# C51_led.net
KiCad netlist of a schematic drawn in Altium Designer
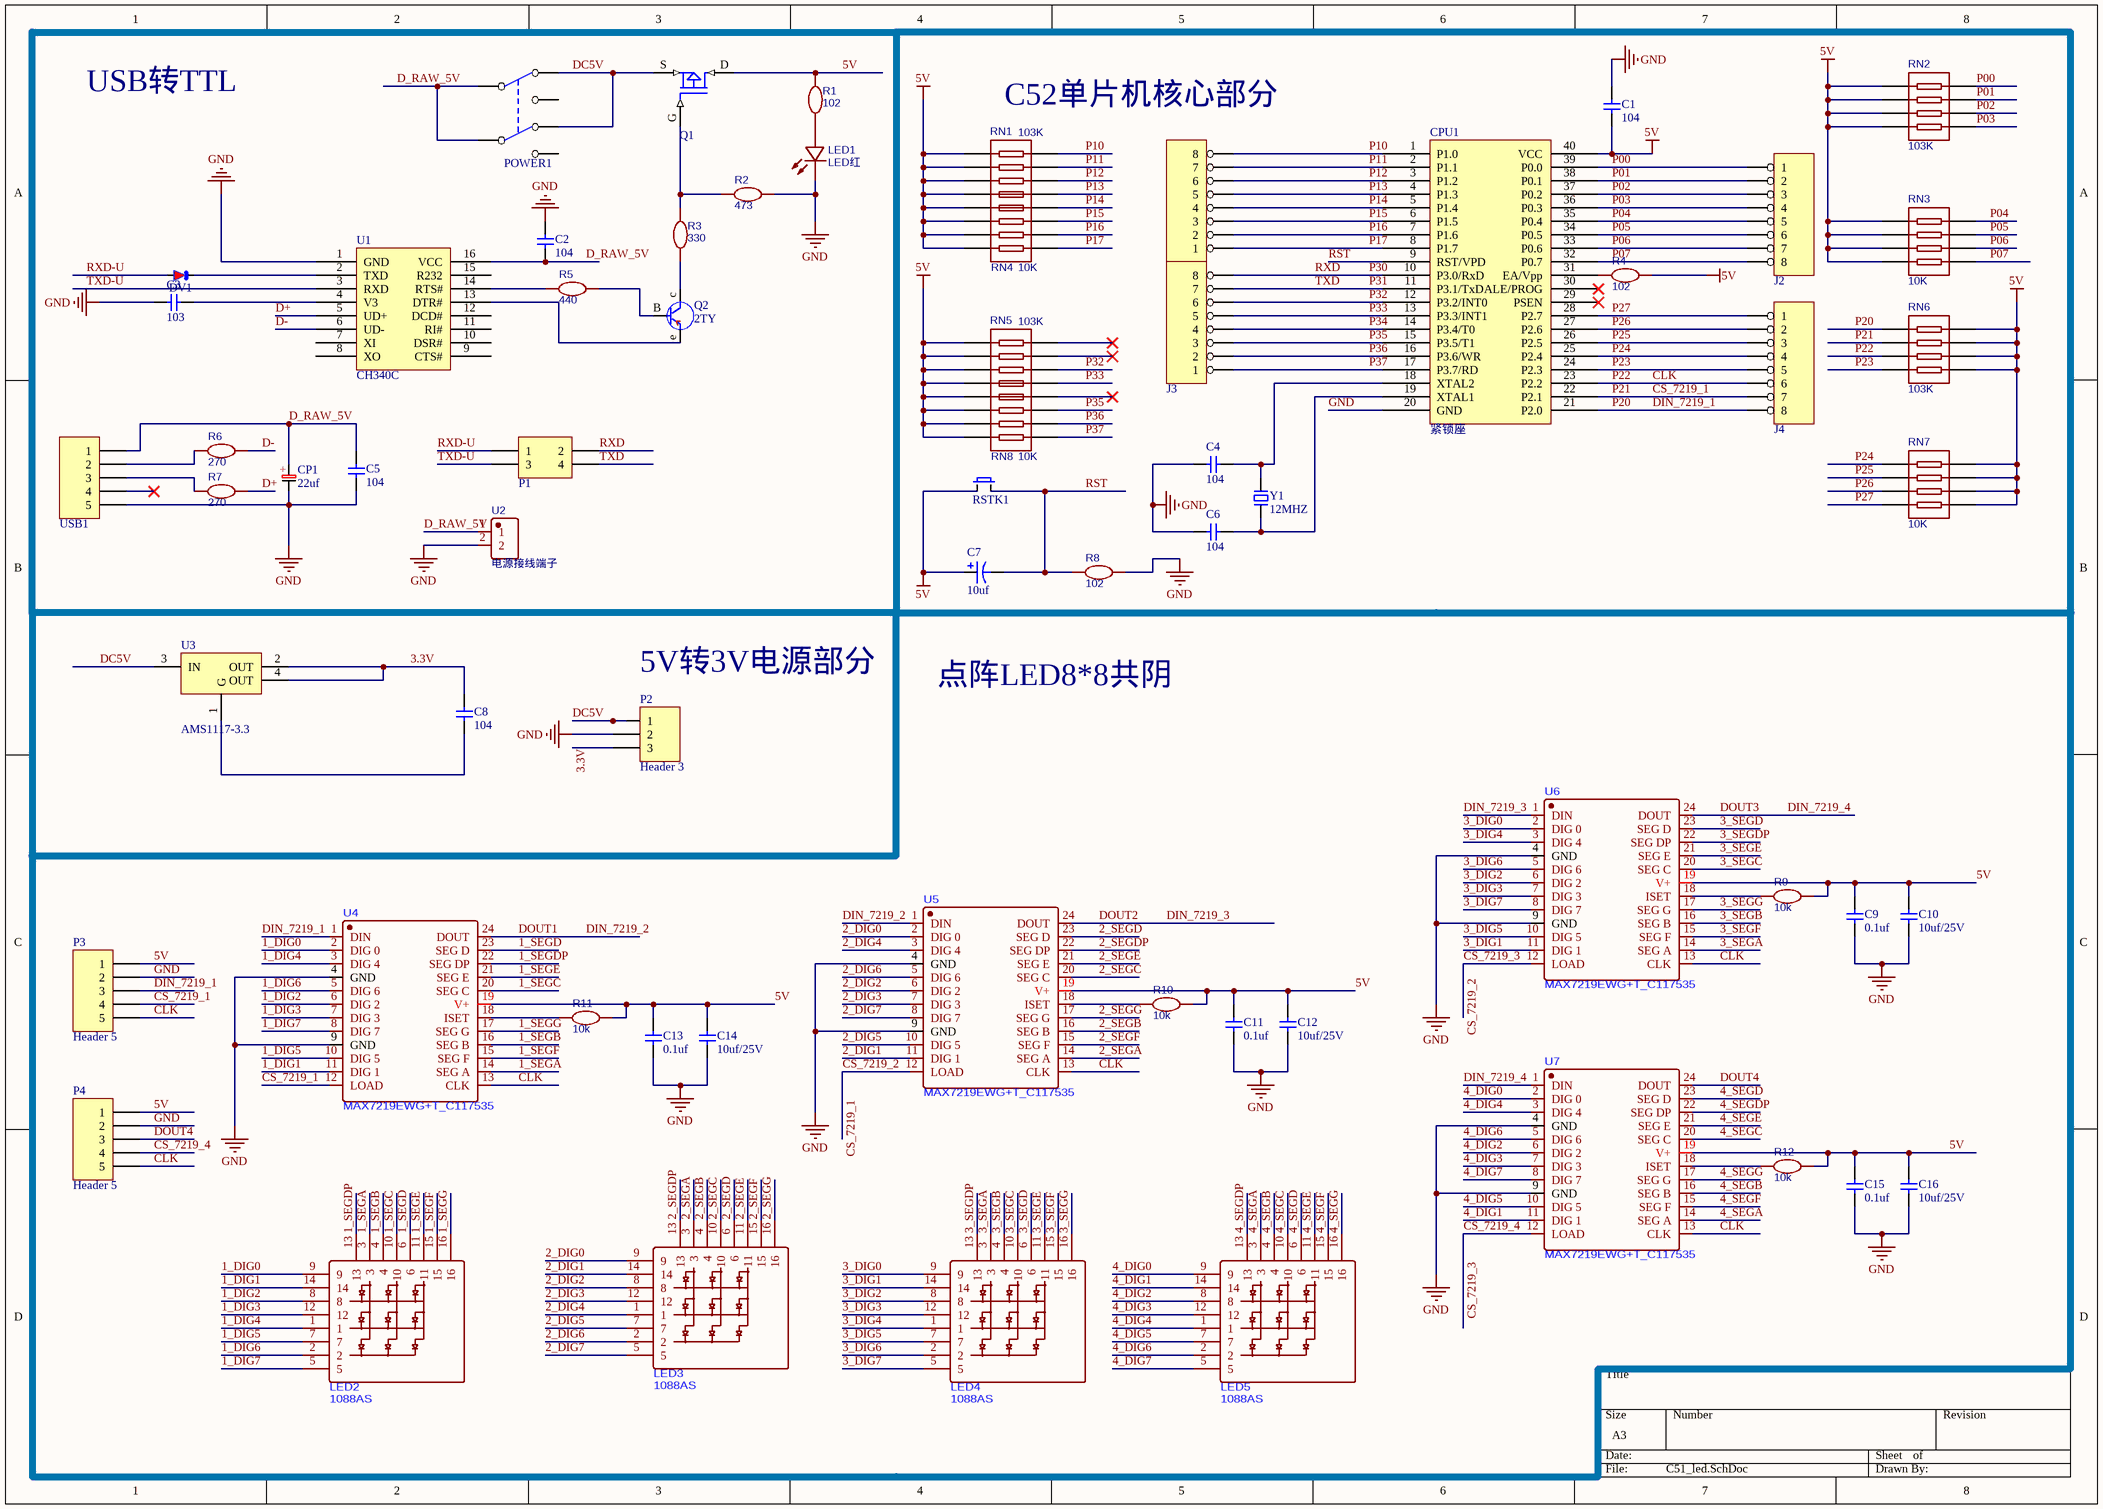
[diagram p0: C51_led.SchDoc]

(export (version "E")
  (design (tool "Eeschema 10.0.6"))
  (components
    (comp (ref "C1") (value "104") (footprint "C1206") (libsource (lib "童有为sch") (part "CAP")))
    (comp (ref "C2") (value "104") (footprint "C1206") (libsource (lib "童有为sch") (part "CAP")))
    (comp (ref "C3") (value "103") (footprint "C1206") (libsource (lib "童有为sch") (part "CAP")))
    (comp (ref "C4") (value "104") (footprint "C1206") (libsource (lib "童有为sch") (part "CAP")))
    (comp (ref "C5") (value "104") (footprint "C1206") (libsource (lib "童有为sch") (part "CAP")))
    (comp (ref "C6") (value "104") (footprint "C1206") (libsource (lib "童有为sch") (part "CAP")))
    (comp (ref "C7")
      (value "10uf")
      (footprint "CD4")
      (description "Polarized Capacitor (Radial)")
      (fields (field (name "PUBLISHER") "*"))
      (libsource (lib "普中-2&普中-3&普中-4封装库") (part "Cap Pol1"))
    )
    (comp (ref "C8") (value "104") (footprint "C1206") (libsource (lib "童有为sch") (part "CAP")))
    (comp (ref "C9") (value "0.1uf") (footprint "C1206") (libsource (lib "童有为sch") (part "CAP")))
    (comp (ref "C10") (value "10uf/25V") (footprint "C1206") (libsource (lib "童有为sch") (part "CAP")))
    (comp (ref "C11") (value "0.1uf") (footprint "C1206") (libsource (lib "童有为sch") (part "CAP")))
    (comp (ref "C12") (value "10uf/25V") (footprint "C1206") (libsource (lib "童有为sch") (part "CAP")))
    (comp (ref "C13") (value "0.1uf") (footprint "C1206") (libsource (lib "童有为sch") (part "CAP")))
    (comp (ref "C14") (value "10uf/25V") (footprint "C1206") (libsource (lib "童有为sch") (part "CAP")))
    (comp (ref "C15") (value "0.1uf") (footprint "C1206") (libsource (lib "童有为sch") (part "CAP")))
    (comp (ref "C16") (value "10uf/25V") (footprint "C1206") (libsource (lib "童有为sch") (part "CAP")))
    (comp (ref "CP1") (value "22uf") (footprint "CD4") (libsource (lib "普中-2&普中-3&普中-4封装库") (part "CD")))
    (comp (ref "CPU1")
      (value "紧锁座")
      (footprint "ZIF40 - D")
      (description "U")
      (libsource (lib "普中-2&普中-3&普中-4封装库") (part "89C51"))
    )
    (comp (ref "DV1") (value "IN4148") (footprint "D1808A") (libsource (lib "普中-2&普中-3&普中-4封装库") (part "D")))
    (comp (ref "J1")
      (value "SIP8")
      (footprint "SIP8")
      (description "8 Pin Header")
      (libsource (lib "普中-2&普中-3&普中-4封装库") (part "8 HEADER"))
    )
    (comp (ref "J2")
      (value "SIP8")
      (footprint "SIP8")
      (description "8 Pin Header")
      (libsource (lib "") (part "8 HEADER_1"))
    )
    (comp (ref "J3")
      (value "SIP8")
      (footprint "SIP8")
      (description "8 Pin Header")
      (libsource (lib "普中-2&普中-3&普中-4封装库") (part "8 HEADER"))
    )
    (comp (ref "J4")
      (value "SIP8")
      (footprint "SIP8")
      (description "8 Pin Header")
      (libsource (lib "") (part "8 HEADER_1"))
    )
    (comp (ref "LED1")
      (value "LED红")
      (footprint "LED1206-R-RD")
      (fields
        (field (name "BOM_SUPPLIER PART") "C268276")
        (field (name "BOM_MANUFACTURER PART") "OSR51206C1E")
        (field (name "CONTRIBUTOR") "LCSC")
      )
      (libsource (lib "LED_1206") (part "OSR51206C1E"))
    )
    (comp (ref "LED2") (value "1088AS") (footprint "1088AS") (libsource (lib "1088AS") (part "1088AS")))
    (comp (ref "LED3") (value "1088AS") (footprint "1088AS") (libsource (lib "1088AS") (part "1088AS")))
    (comp (ref "LED4") (value "1088AS") (footprint "1088AS") (libsource (lib "1088AS") (part "1088AS")))
    (comp (ref "LED5") (value "1088AS") (footprint "1088AS") (libsource (lib "1088AS") (part "1088AS")))
    (comp (ref "P1")
      (value "Header 2X2")
      (footprint "HDR2X2")
      (description "Header, 2-Pin, Dual row")
      (fields (field (name "PUBLISHER") "Altium Limited"))
      (libsource (lib "普中-2&普中-3&普中-4封装库") (part "Header 2X2"))
    )
    (comp (ref "P2")
      (value "Header 3")
      (footprint "HDR1X3")
      (description "Header, 3-Pin")
      (fields (field (name "PUBLISHER") "Altium Limited"))
      (libsource (lib "常用元件2") (part "Header 3"))
    )
    (comp (ref "P3")
      (value "Header 5")
      (footprint "HDR1X5")
      (description "Header, 5-Pin")
      (fields (field (name "PUBLISHER") "Altium Limited"))
      (libsource (lib "常用元件2") (part "Header 5"))
    )
    (comp (ref "P4")
      (value "Header 5")
      (footprint "HDR1X5")
      (description "Header, 5-Pin")
      (fields (field (name "PUBLISHER") "Altium Limited"))
      (libsource (lib "常用元件2") (part "Header 5"))
    )
    (comp (ref "POWER1")
      (value "自锁开关")
      (footprint "SW6")
      (libsource (lib "普中-2&普中-3&普中-4封装库") (part "SW3-DP"))
    )
    (comp (ref "Q1") (value "MOS-P") (footprint "MOS-P") (libsource (lib "普中-2&普中-3&普中-4封装库") (part "MOS-P")))
    (comp (ref "Q2") (value "2TY") (footprint "NPN-2TY") (libsource (lib "普中-2&普中-3&普中-4封装库") (part "8550")))
    (comp (ref "R1")
      (value "102")
      (footprint "R1206")
      (fields
        (field (name "BOM_SUPPLIER PART") "C125917")
        (field (name "BOM_MANUFACTURER PART") "AC1206FR-072ML")
        (field (name "CONTRIBUTOR") "LCSC")
      )
      (libsource (lib "res_1206") (part "AC1206FR-072ML"))
    )
    (comp (ref "R2")
      (value "473")
      (footprint "R1206")
      (fields
        (field (name "BOM_SUPPLIER PART") "C125917")
        (field (name "BOM_MANUFACTURER PART") "AC1206FR-072ML")
        (field (name "CONTRIBUTOR") "LCSC")
      )
      (libsource (lib "res_1206") (part "AC1206FR-072ML"))
    )
    (comp (ref "R3")
      (value "330")
      (footprint "R1206")
      (fields
        (field (name "BOM_SUPPLIER PART") "C125917")
        (field (name "BOM_MANUFACTURER PART") "AC1206FR-072ML")
        (field (name "CONTRIBUTOR") "LCSC")
      )
      (libsource (lib "res_1206") (part "AC1206FR-072ML"))
    )
    (comp (ref "R4")
      (value "102")
      (footprint "R1206")
      (fields
        (field (name "BOM_SUPPLIER PART") "C125917")
        (field (name "BOM_MANUFACTURER PART") "AC1206FR-072ML")
        (field (name "CONTRIBUTOR") "LCSC")
      )
      (libsource (lib "res_1206") (part "AC1206FR-072ML"))
    )
    (comp (ref "R5")
      (value "440")
      (footprint "R1206")
      (fields
        (field (name "BOM_SUPPLIER PART") "C125917")
        (field (name "BOM_MANUFACTURER PART") "AC1206FR-072ML")
        (field (name "CONTRIBUTOR") "LCSC")
      )
      (libsource (lib "res_1206") (part "AC1206FR-072ML"))
    )
    (comp (ref "R6")
      (value "270")
      (footprint "R1206")
      (fields
        (field (name "BOM_SUPPLIER PART") "C125917")
        (field (name "BOM_MANUFACTURER PART") "AC1206FR-072ML")
        (field (name "CONTRIBUTOR") "LCSC")
      )
      (libsource (lib "res_1206") (part "AC1206FR-072ML"))
    )
    (comp (ref "R7")
      (value "270")
      (footprint "R1206")
      (fields
        (field (name "BOM_SUPPLIER PART") "C125917")
        (field (name "BOM_MANUFACTURER PART") "AC1206FR-072ML")
        (field (name "CONTRIBUTOR") "LCSC")
      )
      (libsource (lib "res_1206") (part "AC1206FR-072ML"))
    )
    (comp (ref "R8")
      (value "102")
      (footprint "R1206")
      (fields
        (field (name "BOM_SUPPLIER PART") "C125917")
        (field (name "BOM_MANUFACTURER PART") "AC1206FR-072ML")
        (field (name "CONTRIBUTOR") "LCSC")
      )
      (libsource (lib "res_1206") (part "AC1206FR-072ML"))
    )
    (comp (ref "R9")
      (value "10k")
      (footprint "R1206")
      (fields
        (field (name "BOM_SUPPLIER PART") "C125917")
        (field (name "BOM_MANUFACTURER PART") "AC1206FR-072ML")
        (field (name "CONTRIBUTOR") "LCSC")
      )
      (libsource (lib "res_1206") (part "AC1206FR-072ML"))
    )
    (comp (ref "R10")
      (value "10k")
      (footprint "R1206")
      (fields
        (field (name "BOM_SUPPLIER PART") "C125917")
        (field (name "BOM_MANUFACTURER PART") "AC1206FR-072ML")
        (field (name "CONTRIBUTOR") "LCSC")
      )
      (libsource (lib "res_1206") (part "AC1206FR-072ML"))
    )
    (comp (ref "R11")
      (value "10k")
      (footprint "R1206")
      (fields
        (field (name "BOM_SUPPLIER PART") "C125917")
        (field (name "BOM_MANUFACTURER PART") "AC1206FR-072ML")
        (field (name "CONTRIBUTOR") "LCSC")
      )
      (libsource (lib "res_1206") (part "AC1206FR-072ML"))
    )
    (comp (ref "R12")
      (value "10k")
      (footprint "R1206")
      (fields
        (field (name "BOM_SUPPLIER PART") "C125917")
        (field (name "BOM_MANUFACTURER PART") "AC1206FR-072ML")
        (field (name "CONTRIBUTOR") "LCSC")
      )
      (libsource (lib "res_1206") (part "AC1206FR-072ML"))
    )
    (comp (ref "RN1")
      (value "103K")
      (footprint "RES-ARRAY-SMD_0603-8P-L3.2-W1.6-BL")
      (fields
        (field (name "BOM_MANUFACTURER PART") "4D03WGJ0302T5E")
        (field (name "BOM_SUPPLIER PART") "C25733")
      )
      (libsource (lib "排阻res") (part "3K"))
    )
    (comp (ref "RN2")
      (value "103K")
      (footprint "RES-ARRAY-SMD_0603-8P-L3.2-W1.6-BL")
      (fields
        (field (name "BOM_MANUFACTURER PART") "4D03WGJ0302T5E")
        (field (name "BOM_SUPPLIER PART") "C25733")
      )
      (libsource (lib "排阻res") (part "3K"))
    )
    (comp (ref "RN3")
      (value "10K")
      (footprint "RES-ARRAY-SMD_0603-8P-L3.2-W1.6-BL")
      (fields
        (field (name "BOM_MANUFACTURER PART") "4D03WGJ0302T5E")
        (field (name "BOM_SUPPLIER PART") "C25733")
      )
      (libsource (lib "排阻res") (part "3K"))
    )
    (comp (ref "RN4")
      (value "10K")
      (footprint "RES-ARRAY-SMD_0603-8P-L3.2-W1.6-BL")
      (fields
        (field (name "BOM_MANUFACTURER PART") "4D03WGJ0302T5E")
        (field (name "BOM_SUPPLIER PART") "C25733")
      )
      (libsource (lib "排阻res") (part "3K"))
    )
    (comp (ref "RN5")
      (value "103K")
      (footprint "RES-ARRAY-SMD_0603-8P-L3.2-W1.6-BL")
      (fields
        (field (name "BOM_MANUFACTURER PART") "4D03WGJ0302T5E")
        (field (name "BOM_SUPPLIER PART") "C25733")
      )
      (libsource (lib "排阻res") (part "3K"))
    )
    (comp (ref "RN6")
      (value "103K")
      (footprint "RES-ARRAY-SMD_0603-8P-L3.2-W1.6-BL")
      (fields
        (field (name "BOM_MANUFACTURER PART") "4D03WGJ0302T5E")
        (field (name "BOM_SUPPLIER PART") "C25733")
      )
      (libsource (lib "排阻res") (part "3K"))
    )
    (comp (ref "RN7")
      (value "10K")
      (footprint "RES-ARRAY-SMD_0603-8P-L3.2-W1.6-BL")
      (fields
        (field (name "BOM_MANUFACTURER PART") "4D03WGJ0302T5E")
        (field (name "BOM_SUPPLIER PART") "C25733")
      )
      (libsource (lib "排阻res") (part "3K"))
    )
    (comp (ref "RN8")
      (value "10K")
      (footprint "RES-ARRAY-SMD_0603-8P-L3.2-W1.6-BL")
      (fields
        (field (name "BOM_MANUFACTURER PART") "4D03WGJ0302T5E")
        (field (name "BOM_SUPPLIER PART") "C25733")
      )
      (libsource (lib "排阻res") (part "3K"))
    )
    (comp (ref "RSTK1")
      (value "按键")
      (footprint "JZ-SW2")
      (libsource (lib "普中-2&普中-3&普中-4封装库") (part "JZ-SW2"))
    )
    (comp (ref "U1")
      (value "CH340C")
      (footprint "SOP-16")
      (libsource (lib "普中-2&普中-3&普中-4封装库") (part "CH340G"))
    )
    (comp (ref "U2")
      (value "电源接线端子")
      (footprint "2p_power")
      (fields
        (field (name "BOM_SUPPLIER PART") "C581335")
        (field (name "BOM_MANUFACTURER PART") "DG127R-5.0-02P-14-00A(H)")
        (field (name "CONTRIBUTOR") "LCSC")
      )
      (libsource (lib "接线端子p=5") (part "DG127R-5.0-02P-14-00A(H)"))
    )
    (comp (ref "U3")
      (value "AMS1117-3.3")
      (footprint "SOT261")
      (description "LINER REG")
      (libsource (lib "普中-2&普中-3&普中-4封装库") (part "LM1117"))
    )
    (comp (ref "U4")
      (value "MAX7219EWG+T_C117535")
      (footprint "sop-24")
      (libsource (lib "max7219") (part "MAX7219EWG+T_C117535"))
    )
    (comp (ref "U5")
      (value "MAX7219EWG+T_C117535")
      (footprint "sop-24")
      (libsource (lib "max7219") (part "MAX7219EWG+T_C117535"))
    )
    (comp (ref "U6")
      (value "MAX7219EWG+T_C117535")
      (footprint "sop-24")
      (libsource (lib "max7219") (part "MAX7219EWG+T_C117535"))
    )
    (comp (ref "U7")
      (value "MAX7219EWG+T_C117535")
      (footprint "sop-24")
      (libsource (lib "max7219") (part "MAX7219EWG+T_C117535"))
    )
    (comp (ref "USB1")
      (value "MiniUSB")
      (footprint "MINIUSB_5PIN_4Pad_New")
      (description "Header, 5-Pin")
      (fields (field (name "PUBLISHER") "Altium Limited"))
      (libsource (lib "普中-2&普中-3&普中-4封装库") (part "Header 5"))
    )
    (comp (ref "Y1") (value "12MHZ") (footprint "CC0.254") (libsource (lib "普中-2&普中-3&普中-4封装库") (part "JT")))
  )
  (nets
    (net (code "1") (name "/1_DIG0") (class "Default")
      (node (ref "LED2") (pin "9") (pinfunction "9_9") (pintype "passive"))
      (node (ref "U4") (pin "2") (pinfunction "DIG_0_2") (pintype "passive"))
    )
    (net (code "2") (name "/1_DIG1") (class "Default")
      (node (ref "LED2") (pin "14") (pinfunction "14_14") (pintype "passive"))
      (node (ref "U4") (pin "11") (pinfunction "DIG_1_11") (pintype "passive"))
    )
    (net (code "3") (name "/1_DIG2") (class "Default")
      (node (ref "LED2") (pin "8") (pinfunction "8_8") (pintype "passive"))
      (node (ref "U4") (pin "6") (pinfunction "DIG_2_6") (pintype "passive"))
    )
    (net (code "4") (name "/1_DIG3") (class "Default")
      (node (ref "LED2") (pin "12") (pinfunction "12_12") (pintype "passive"))
      (node (ref "U4") (pin "7") (pinfunction "DIG_3_7") (pintype "passive"))
    )
    (net (code "5") (name "/1_DIG4") (class "Default")
      (node (ref "LED2") (pin "1") (pinfunction "1_1") (pintype "passive"))
      (node (ref "U4") (pin "3") (pinfunction "DIG_4_3") (pintype "passive"))
    )
    (net (code "6") (name "/1_DIG5") (class "Default")
      (node (ref "LED2") (pin "7") (pinfunction "7_7") (pintype "passive"))
      (node (ref "U4") (pin "10") (pinfunction "DIG_5_10") (pintype "passive"))
    )
    (net (code "7") (name "/1_DIG6") (class "Default")
      (node (ref "LED2") (pin "2") (pinfunction "2_2") (pintype "passive"))
      (node (ref "U4") (pin "5") (pinfunction "DIG_6_5") (pintype "passive"))
    )
    (net (code "8") (name "/1_DIG7") (class "Default")
      (node (ref "LED2") (pin "5") (pinfunction "5_5") (pintype "passive"))
      (node (ref "U4") (pin "8") (pinfunction "DIG_7_8") (pintype "passive"))
    )
    (net (code "9") (name "/1_SEGA") (class "Default")
      (node (ref "LED2") (pin "3") (pinfunction "3_3") (pintype "passive"))
      (node (ref "U4") (pin "14") (pinfunction "SEG_A_14") (pintype "passive"))
    )
    (net (code "10") (name "/1_SEGB") (class "Default")
      (node (ref "LED2") (pin "4") (pinfunction "4_4") (pintype "passive"))
      (node (ref "U4") (pin "16") (pinfunction "SEG_B_16") (pintype "passive"))
    )
    (net (code "11") (name "/1_SEGC") (class "Default")
      (node (ref "LED2") (pin "10") (pinfunction "10_10") (pintype "passive"))
      (node (ref "U4") (pin "20") (pinfunction "SEG_C_20") (pintype "passive"))
    )
    (net (code "12") (name "/1_SEGD") (class "Default")
      (node (ref "LED2") (pin "6") (pinfunction "6_6") (pintype "passive"))
      (node (ref "U4") (pin "23") (pinfunction "SEG_D_23") (pintype "passive"))
    )
    (net (code "13") (name "/1_SEGDP") (class "Default")
      (node (ref "LED2") (pin "13") (pinfunction "13_13") (pintype "passive"))
      (node (ref "U4") (pin "22") (pinfunction "SEG_DP_22") (pintype "passive"))
    )
    (net (code "14") (name "/1_SEGE") (class "Default")
      (node (ref "LED2") (pin "11") (pinfunction "11_11") (pintype "passive"))
      (node (ref "U4") (pin "21") (pinfunction "SEG_E_21") (pintype "passive"))
    )
    (net (code "15") (name "/1_SEGF") (class "Default")
      (node (ref "LED2") (pin "15") (pinfunction "15_15") (pintype "passive"))
      (node (ref "U4") (pin "15") (pinfunction "SEG_F_15") (pintype "passive"))
    )
    (net (code "16") (name "/1_SEGG") (class "Default")
      (node (ref "LED2") (pin "16") (pinfunction "16_16") (pintype "passive"))
      (node (ref "U4") (pin "17") (pinfunction "SEG_G_17") (pintype "passive"))
    )
    (net (code "17") (name "/2_DIG0") (class "Default")
      (node (ref "LED3") (pin "9") (pinfunction "9_9") (pintype "passive"))
      (node (ref "U5") (pin "2") (pinfunction "DIG_0_2") (pintype "passive"))
    )
    (net (code "18") (name "/2_DIG1") (class "Default")
      (node (ref "LED3") (pin "14") (pinfunction "14_14") (pintype "passive"))
      (node (ref "U5") (pin "11") (pinfunction "DIG_1_11") (pintype "passive"))
    )
    (net (code "19") (name "/2_DIG2") (class "Default")
      (node (ref "LED3") (pin "8") (pinfunction "8_8") (pintype "passive"))
      (node (ref "U5") (pin "6") (pinfunction "DIG_2_6") (pintype "passive"))
    )
    (net (code "20") (name "/2_DIG3") (class "Default")
      (node (ref "LED3") (pin "12") (pinfunction "12_12") (pintype "passive"))
      (node (ref "U5") (pin "7") (pinfunction "DIG_3_7") (pintype "passive"))
    )
    (net (code "21") (name "/2_DIG4") (class "Default")
      (node (ref "LED3") (pin "1") (pinfunction "1_1") (pintype "passive"))
      (node (ref "U5") (pin "3") (pinfunction "DIG_4_3") (pintype "passive"))
    )
    (net (code "22") (name "/2_DIG5") (class "Default")
      (node (ref "LED3") (pin "7") (pinfunction "7_7") (pintype "passive"))
      (node (ref "U5") (pin "10") (pinfunction "DIG_5_10") (pintype "passive"))
    )
    (net (code "23") (name "/2_DIG6") (class "Default")
      (node (ref "LED3") (pin "2") (pinfunction "2_2") (pintype "passive"))
      (node (ref "U5") (pin "5") (pinfunction "DIG_6_5") (pintype "passive"))
    )
    (net (code "24") (name "/2_DIG7") (class "Default")
      (node (ref "LED3") (pin "5") (pinfunction "5_5") (pintype "passive"))
      (node (ref "U5") (pin "8") (pinfunction "DIG_7_8") (pintype "passive"))
    )
    (net (code "25") (name "/2_SEGA") (class "Default")
      (node (ref "LED3") (pin "3") (pinfunction "3_3") (pintype "passive"))
      (node (ref "U5") (pin "14") (pinfunction "SEG_A_14") (pintype "passive"))
    )
    (net (code "26") (name "/2_SEGB") (class "Default")
      (node (ref "LED3") (pin "4") (pinfunction "4_4") (pintype "passive"))
      (node (ref "U5") (pin "16") (pinfunction "SEG_B_16") (pintype "passive"))
    )
    (net (code "27") (name "/2_SEGC") (class "Default")
      (node (ref "LED3") (pin "10") (pinfunction "10_10") (pintype "passive"))
      (node (ref "U5") (pin "20") (pinfunction "SEG_C_20") (pintype "passive"))
    )
    (net (code "28") (name "/2_SEGD") (class "Default")
      (node (ref "LED3") (pin "6") (pinfunction "6_6") (pintype "passive"))
      (node (ref "U5") (pin "23") (pinfunction "SEG_D_23") (pintype "passive"))
    )
    (net (code "29") (name "/2_SEGDP") (class "Default")
      (node (ref "LED3") (pin "13") (pinfunction "13_13") (pintype "passive"))
      (node (ref "U5") (pin "22") (pinfunction "SEG_DP_22") (pintype "passive"))
    )
    (net (code "30") (name "/2_SEGE") (class "Default")
      (node (ref "LED3") (pin "11") (pinfunction "11_11") (pintype "passive"))
      (node (ref "U5") (pin "21") (pinfunction "SEG_E_21") (pintype "passive"))
    )
    (net (code "31") (name "/2_SEGF") (class "Default")
      (node (ref "LED3") (pin "15") (pinfunction "15_15") (pintype "passive"))
      (node (ref "U5") (pin "15") (pinfunction "SEG_F_15") (pintype "passive"))
    )
    (net (code "32") (name "/2_SEGG") (class "Default")
      (node (ref "LED3") (pin "16") (pinfunction "16_16") (pintype "passive"))
      (node (ref "U5") (pin "17") (pinfunction "SEG_G_17") (pintype "passive"))
    )
    (net (code "33") (name "/3.3V") (class "Default")
      (node (ref "C8") (pin "2") (pintype "passive"))
      (node (ref "P2") (pin "3") (pinfunction "3_3") (pintype "passive"))
      (node (ref "U3") (pin "2") (pinfunction "OUT_2") (pintype "passive"))
      (node (ref "U3") (pin "4") (pinfunction "OUT_4") (pintype "passive"))
    )
    (net (code "34") (name "/3_DIG0") (class "Default")
      (node (ref "LED4") (pin "9") (pinfunction "9_9") (pintype "passive"))
      (node (ref "U6") (pin "2") (pinfunction "DIG_0_2") (pintype "passive"))
    )
    (net (code "35") (name "/3_DIG1") (class "Default")
      (node (ref "LED4") (pin "14") (pinfunction "14_14") (pintype "passive"))
      (node (ref "U6") (pin "11") (pinfunction "DIG_1_11") (pintype "passive"))
    )
    (net (code "36") (name "/3_DIG2") (class "Default")
      (node (ref "LED4") (pin "8") (pinfunction "8_8") (pintype "passive"))
      (node (ref "U6") (pin "6") (pinfunction "DIG_2_6") (pintype "passive"))
    )
    (net (code "37") (name "/3_DIG3") (class "Default")
      (node (ref "LED4") (pin "12") (pinfunction "12_12") (pintype "passive"))
      (node (ref "U6") (pin "7") (pinfunction "DIG_3_7") (pintype "passive"))
    )
    (net (code "38") (name "/3_DIG4") (class "Default")
      (node (ref "LED4") (pin "1") (pinfunction "1_1") (pintype "passive"))
      (node (ref "U6") (pin "3") (pinfunction "DIG_4_3") (pintype "passive"))
    )
    (net (code "39") (name "/3_DIG5") (class "Default")
      (node (ref "LED4") (pin "7") (pinfunction "7_7") (pintype "passive"))
      (node (ref "U6") (pin "10") (pinfunction "DIG_5_10") (pintype "passive"))
    )
    (net (code "40") (name "/3_DIG6") (class "Default")
      (node (ref "LED4") (pin "2") (pinfunction "2_2") (pintype "passive"))
      (node (ref "U6") (pin "5") (pinfunction "DIG_6_5") (pintype "passive"))
    )
    (net (code "41") (name "/3_DIG7") (class "Default")
      (node (ref "LED4") (pin "5") (pinfunction "5_5") (pintype "passive"))
      (node (ref "U6") (pin "8") (pinfunction "DIG_7_8") (pintype "passive"))
    )
    (net (code "42") (name "/3_SEGA") (class "Default")
      (node (ref "LED4") (pin "3") (pinfunction "3_3") (pintype "passive"))
      (node (ref "U6") (pin "14") (pinfunction "SEG_A_14") (pintype "passive"))
    )
    (net (code "43") (name "/3_SEGB") (class "Default")
      (node (ref "LED4") (pin "4") (pinfunction "4_4") (pintype "passive"))
      (node (ref "U6") (pin "16") (pinfunction "SEG_B_16") (pintype "passive"))
    )
    (net (code "44") (name "/3_SEGC") (class "Default")
      (node (ref "LED4") (pin "10") (pinfunction "10_10") (pintype "passive"))
      (node (ref "U6") (pin "20") (pinfunction "SEG_C_20") (pintype "passive"))
    )
    (net (code "45") (name "/3_SEGD") (class "Default")
      (node (ref "LED4") (pin "6") (pinfunction "6_6") (pintype "passive"))
      (node (ref "U6") (pin "23") (pinfunction "SEG_D_23") (pintype "passive"))
    )
    (net (code "46") (name "/3_SEGDP") (class "Default")
      (node (ref "LED4") (pin "13") (pinfunction "13_13") (pintype "passive"))
      (node (ref "U6") (pin "22") (pinfunction "SEG_DP_22") (pintype "passive"))
    )
    (net (code "47") (name "/3_SEGE") (class "Default")
      (node (ref "LED4") (pin "11") (pinfunction "11_11") (pintype "passive"))
      (node (ref "U6") (pin "21") (pinfunction "SEG_E_21") (pintype "passive"))
    )
    (net (code "48") (name "/3_SEGF") (class "Default")
      (node (ref "LED4") (pin "15") (pinfunction "15_15") (pintype "passive"))
      (node (ref "U6") (pin "15") (pinfunction "SEG_F_15") (pintype "passive"))
    )
    (net (code "49") (name "/3_SEGG") (class "Default")
      (node (ref "LED4") (pin "16") (pinfunction "16_16") (pintype "passive"))
      (node (ref "U6") (pin "17") (pinfunction "SEG_G_17") (pintype "passive"))
    )
    (net (code "50") (name "/4_DIG0") (class "Default")
      (node (ref "LED5") (pin "9") (pinfunction "9_9") (pintype "passive"))
      (node (ref "U7") (pin "2") (pinfunction "DIG_0_2") (pintype "passive"))
    )
    (net (code "51") (name "/4_DIG1") (class "Default")
      (node (ref "LED5") (pin "14") (pinfunction "14_14") (pintype "passive"))
      (node (ref "U7") (pin "11") (pinfunction "DIG_1_11") (pintype "passive"))
    )
    (net (code "52") (name "/4_DIG2") (class "Default")
      (node (ref "LED5") (pin "8") (pinfunction "8_8") (pintype "passive"))
      (node (ref "U7") (pin "6") (pinfunction "DIG_2_6") (pintype "passive"))
    )
    (net (code "53") (name "/4_DIG3") (class "Default")
      (node (ref "LED5") (pin "12") (pinfunction "12_12") (pintype "passive"))
      (node (ref "U7") (pin "7") (pinfunction "DIG_3_7") (pintype "passive"))
    )
    (net (code "54") (name "/4_DIG4") (class "Default")
      (node (ref "LED5") (pin "1") (pinfunction "1_1") (pintype "passive"))
      (node (ref "U7") (pin "3") (pinfunction "DIG_4_3") (pintype "passive"))
    )
    (net (code "55") (name "/4_DIG5") (class "Default")
      (node (ref "LED5") (pin "7") (pinfunction "7_7") (pintype "passive"))
      (node (ref "U7") (pin "10") (pinfunction "DIG_5_10") (pintype "passive"))
    )
    (net (code "56") (name "/4_DIG6") (class "Default")
      (node (ref "LED5") (pin "2") (pinfunction "2_2") (pintype "passive"))
      (node (ref "U7") (pin "5") (pinfunction "DIG_6_5") (pintype "passive"))
    )
    (net (code "57") (name "/4_DIG7") (class "Default")
      (node (ref "LED5") (pin "5") (pinfunction "5_5") (pintype "passive"))
      (node (ref "U7") (pin "8") (pinfunction "DIG_7_8") (pintype "passive"))
    )
    (net (code "58") (name "/4_SEGA") (class "Default")
      (node (ref "LED5") (pin "3") (pinfunction "3_3") (pintype "passive"))
      (node (ref "U7") (pin "14") (pinfunction "SEG_A_14") (pintype "passive"))
    )
    (net (code "59") (name "/4_SEGB") (class "Default")
      (node (ref "LED5") (pin "4") (pinfunction "4_4") (pintype "passive"))
      (node (ref "U7") (pin "16") (pinfunction "SEG_B_16") (pintype "passive"))
    )
    (net (code "60") (name "/4_SEGC") (class "Default")
      (node (ref "LED5") (pin "10") (pinfunction "10_10") (pintype "passive"))
      (node (ref "U7") (pin "20") (pinfunction "SEG_C_20") (pintype "passive"))
    )
    (net (code "61") (name "/4_SEGD") (class "Default")
      (node (ref "LED5") (pin "6") (pinfunction "6_6") (pintype "passive"))
      (node (ref "U7") (pin "23") (pinfunction "SEG_D_23") (pintype "passive"))
    )
    (net (code "62") (name "/4_SEGDP") (class "Default")
      (node (ref "LED5") (pin "13") (pinfunction "13_13") (pintype "passive"))
      (node (ref "U7") (pin "22") (pinfunction "SEG_DP_22") (pintype "passive"))
    )
    (net (code "63") (name "/4_SEGE") (class "Default")
      (node (ref "LED5") (pin "11") (pinfunction "11_11") (pintype "passive"))
      (node (ref "U7") (pin "21") (pinfunction "SEG_E_21") (pintype "passive"))
    )
    (net (code "64") (name "/4_SEGF") (class "Default")
      (node (ref "LED5") (pin "15") (pinfunction "15_15") (pintype "passive"))
      (node (ref "U7") (pin "15") (pinfunction "SEG_F_15") (pintype "passive"))
    )
    (net (code "65") (name "/4_SEGG") (class "Default")
      (node (ref "LED5") (pin "16") (pinfunction "16_16") (pintype "passive"))
      (node (ref "U7") (pin "17") (pinfunction "SEG_G_17") (pintype "passive"))
    )
    (net (code "66") (name "/CLK") (class "Default")
      (node (ref "CPU1") (pin "23") (pinfunction "P2.2_23") (pintype "passive"))
      (node (ref "J4") (pin "6") (pinfunction "6_6") (pintype "passive"))
      (node (ref "P3") (pin "5") (pinfunction "5_5") (pintype "passive"))
      (node (ref "P4") (pin "5") (pinfunction "5_5") (pintype "passive"))
      (node (ref "RN6") (pin "6") (pinfunction "6_6") (pintype "passive"))
      (node (ref "U4") (pin "13") (pinfunction "CLK_13") (pintype "passive"))
      (node (ref "U5") (pin "13") (pinfunction "CLK_13") (pintype "passive"))
      (node (ref "U6") (pin "13") (pinfunction "CLK_13") (pintype "passive"))
      (node (ref "U7") (pin "13") (pinfunction "CLK_13") (pintype "passive"))
    )
    (net (code "67") (name "/CS_7219_1") (class "Default")
      (node (ref "CPU1") (pin "22") (pinfunction "P2.1_22") (pintype "passive"))
      (node (ref "J4") (pin "7") (pinfunction "7_7") (pintype "passive"))
      (node (ref "P3") (pin "4") (pinfunction "4_4") (pintype "passive"))
      (node (ref "P4") (pin "4") (pinfunction "4_4") (pintype "passive"))
      (node (ref "RN6") (pin "7") (pinfunction "7_7") (pintype "passive"))
      (node (ref "U4") (pin "12") (pinfunction "LOAD_12") (pintype "passive"))
      (node (ref "U5") (pin "12") (pinfunction "LOAD_12") (pintype "passive"))
      (node (ref "U6") (pin "12") (pinfunction "LOAD_12") (pintype "passive"))
      (node (ref "U7") (pin "12") (pinfunction "LOAD_12") (pintype "passive"))
    )
    (net (code "68") (name "/D+") (class "Default")
      (node (ref "R7") (pin "2") (pinfunction "2_2") (pintype "passive"))
      (node (ref "U1") (pin "5") (pinfunction "UD+_5") (pintype "passive"))
    )
    (net (code "69") (name "/D-") (class "Default")
      (node (ref "R6") (pin "2") (pinfunction "2_2") (pintype "passive"))
      (node (ref "U1") (pin "6") (pinfunction "UD-_6") (pintype "passive"))
    )
    (net (code "70") (name "/DC5V") (class "Default")
      (node (ref "P2") (pin "1") (pinfunction "1_1") (pintype "passive"))
      (node (ref "POWER1") (pin "1") (pinfunction "NC1_1") (pintype "passive"))
      (node (ref "POWER1") (pin "6") (pinfunction "NC2_6") (pintype "passive"))
      (node (ref "Q1") (pin "S") (pinfunction "S_S") (pintype "input"))
      (node (ref "U3") (pin "3") (pinfunction "IN_3") (pintype "passive"))
    )
    (net (code "71") (name "/DIN_7219_1") (class "Default")
      (node (ref "CPU1") (pin "21") (pinfunction "P2.0_21") (pintype "passive"))
      (node (ref "J4") (pin "8") (pinfunction "8_8") (pintype "passive"))
      (node (ref "P3") (pin "3") (pinfunction "3_3") (pintype "passive"))
      (node (ref "RN6") (pin "8") (pinfunction "8_8") (pintype "passive"))
      (node (ref "U4") (pin "1") (pinfunction "DIN_1") (pintype "passive"))
    )
    (net (code "72") (name "/DIN_7219_2") (class "Default")
      (node (ref "U4") (pin "24") (pinfunction "DOUT_24") (pintype "passive"))
      (node (ref "U5") (pin "1") (pinfunction "DIN_1") (pintype "passive"))
    )
    (net (code "73") (name "/DIN_7219_3") (class "Default")
      (node (ref "U5") (pin "24") (pinfunction "DOUT_24") (pintype "passive"))
      (node (ref "U6") (pin "1") (pinfunction "DIN_1") (pintype "passive"))
    )
    (net (code "74") (name "/DIN_7219_4") (class "Default")
      (node (ref "U6") (pin "24") (pinfunction "DOUT_24") (pintype "passive"))
      (node (ref "U7") (pin "1") (pinfunction "DIN_1") (pintype "passive"))
    )
    (net (code "75") (name "/DOUT4") (class "Default")
      (node (ref "P4") (pin "3") (pinfunction "3_3") (pintype "passive"))
      (node (ref "U7") (pin "24") (pinfunction "DOUT_24") (pintype "passive"))
    )
    (net (code "76") (name "/D_RAW_5V") (class "Default")
      (node (ref "C2") (pin "2") (pintype "passive"))
      (node (ref "C5") (pin "2") (pintype "passive"))
      (node (ref "CP1") (pin "1") (pintype "passive"))
      (node (ref "POWER1") (pin "2") (pinfunction "COMMON1_2") (pintype "passive"))
      (node (ref "POWER1") (pin "5") (pinfunction "COMMON2_5") (pintype "passive"))
      (node (ref "U1") (pin "16") (pinfunction "VCC_16") (pintype "passive"))
      (node (ref "U2") (pin "1") (pinfunction "1_1") (pintype "passive"))
      (node (ref "USB1") (pin "1") (pinfunction "1_1") (pintype "passive"))
    )
    (net (code "77") (name "/P00") (class "Default")
      (node (ref "CPU1") (pin "39") (pinfunction "P0.0_39") (pintype "passive"))
      (node (ref "J2") (pin "1") (pinfunction "1_1") (pintype "passive"))
      (node (ref "RN2") (pin "1") (pinfunction "1_1") (pintype "passive"))
    )
    (net (code "78") (name "/P01") (class "Default")
      (node (ref "CPU1") (pin "38") (pinfunction "P0.1_38") (pintype "passive"))
      (node (ref "J2") (pin "2") (pinfunction "2_2") (pintype "passive"))
      (node (ref "RN2") (pin "2") (pinfunction "2_2") (pintype "passive"))
    )
    (net (code "79") (name "/P02") (class "Default")
      (node (ref "CPU1") (pin "37") (pinfunction "P0.2_37") (pintype "passive"))
      (node (ref "J2") (pin "3") (pinfunction "3_3") (pintype "passive"))
      (node (ref "RN2") (pin "3") (pinfunction "3_3") (pintype "passive"))
    )
    (net (code "80") (name "/P03") (class "Default")
      (node (ref "CPU1") (pin "36") (pinfunction "P0.3_36") (pintype "passive"))
      (node (ref "J2") (pin "4") (pinfunction "4_4") (pintype "passive"))
      (node (ref "RN2") (pin "4") (pinfunction "4_4") (pintype "passive"))
    )
    (net (code "81") (name "/P04") (class "Default")
      (node (ref "CPU1") (pin "35") (pinfunction "P0.4_35") (pintype "passive"))
      (node (ref "J2") (pin "5") (pinfunction "5_5") (pintype "passive"))
      (node (ref "RN3") (pin "1") (pinfunction "1_1") (pintype "passive"))
    )
    (net (code "82") (name "/P05") (class "Default")
      (node (ref "CPU1") (pin "34") (pinfunction "P0.5_34") (pintype "passive"))
      (node (ref "J2") (pin "6") (pinfunction "6_6") (pintype "passive"))
      (node (ref "RN3") (pin "2") (pinfunction "2_2") (pintype "passive"))
    )
    (net (code "83") (name "/P06") (class "Default")
      (node (ref "CPU1") (pin "33") (pinfunction "P0.6_33") (pintype "passive"))
      (node (ref "J2") (pin "7") (pinfunction "7_7") (pintype "passive"))
      (node (ref "RN3") (pin "3") (pinfunction "3_3") (pintype "passive"))
    )
    (net (code "84") (name "/P07") (class "Default")
      (node (ref "CPU1") (pin "32") (pinfunction "P0.7_32") (pintype "passive"))
      (node (ref "J2") (pin "8") (pinfunction "8_8") (pintype "passive"))
      (node (ref "RN3") (pin "4") (pinfunction "4_4") (pintype "passive"))
    )
    (net (code "85") (name "/P10") (class "Default")
      (node (ref "CPU1") (pin "1") (pinfunction "P1.0_1") (pintype "passive"))
      (node (ref "J1") (pin "8") (pinfunction "8_8") (pintype "passive"))
      (node (ref "RN1") (pin "8") (pinfunction "8_8") (pintype "passive"))
    )
    (net (code "86") (name "/P11") (class "Default")
      (node (ref "CPU1") (pin "2") (pinfunction "P1.1_2") (pintype "passive"))
      (node (ref "J1") (pin "7") (pinfunction "7_7") (pintype "passive"))
      (node (ref "RN1") (pin "7") (pinfunction "7_7") (pintype "passive"))
    )
    (net (code "87") (name "/P12") (class "Default")
      (node (ref "CPU1") (pin "3") (pinfunction "P1.2_3") (pintype "passive"))
      (node (ref "J1") (pin "6") (pinfunction "6_6") (pintype "passive"))
      (node (ref "RN1") (pin "6") (pinfunction "6_6") (pintype "passive"))
    )
    (net (code "88") (name "/P13") (class "Default")
      (node (ref "CPU1") (pin "4") (pinfunction "P1.3_4") (pintype "passive"))
      (node (ref "J1") (pin "5") (pinfunction "5_5") (pintype "passive"))
      (node (ref "RN1") (pin "5") (pinfunction "5_5") (pintype "passive"))
    )
    (net (code "89") (name "/P14") (class "Default")
      (node (ref "CPU1") (pin "5") (pinfunction "P1.4_5") (pintype "passive"))
      (node (ref "J1") (pin "4") (pinfunction "4_4") (pintype "passive"))
      (node (ref "RN4") (pin "8") (pinfunction "8_8") (pintype "passive"))
    )
    (net (code "90") (name "/P15") (class "Default")
      (node (ref "CPU1") (pin "6") (pinfunction "P1.5_6") (pintype "passive"))
      (node (ref "J1") (pin "3") (pinfunction "3_3") (pintype "passive"))
      (node (ref "RN4") (pin "7") (pinfunction "7_7") (pintype "passive"))
    )
    (net (code "91") (name "/P16") (class "Default")
      (node (ref "CPU1") (pin "7") (pinfunction "P1.6_7") (pintype "passive"))
      (node (ref "J1") (pin "2") (pinfunction "2_2") (pintype "passive"))
      (node (ref "RN4") (pin "6") (pinfunction "6_6") (pintype "passive"))
    )
    (net (code "92") (name "/P17") (class "Default")
      (node (ref "CPU1") (pin "8") (pinfunction "P1.7_8") (pintype "passive"))
      (node (ref "J1") (pin "1") (pinfunction "1_1") (pintype "passive"))
      (node (ref "RN4") (pin "5") (pinfunction "5_5") (pintype "passive"))
    )
    (net (code "93") (name "/P23") (class "Default")
      (node (ref "CPU1") (pin "24") (pinfunction "P2.3_24") (pintype "passive"))
      (node (ref "J4") (pin "5") (pinfunction "5_5") (pintype "passive"))
      (node (ref "RN6") (pin "5") (pinfunction "5_5") (pintype "passive"))
    )
    (net (code "94") (name "/P24") (class "Default")
      (node (ref "CPU1") (pin "25") (pinfunction "P2.4_25") (pintype "passive"))
      (node (ref "J4") (pin "4") (pinfunction "4_4") (pintype "passive"))
      (node (ref "RN7") (pin "8") (pinfunction "8_8") (pintype "passive"))
    )
    (net (code "95") (name "/P25") (class "Default")
      (node (ref "CPU1") (pin "26") (pinfunction "P2.5_26") (pintype "passive"))
      (node (ref "J4") (pin "3") (pinfunction "3_3") (pintype "passive"))
      (node (ref "RN7") (pin "7") (pinfunction "7_7") (pintype "passive"))
    )
    (net (code "96") (name "/P26") (class "Default")
      (node (ref "CPU1") (pin "27") (pinfunction "P2.6_27") (pintype "passive"))
      (node (ref "J4") (pin "2") (pinfunction "2_2") (pintype "passive"))
      (node (ref "RN7") (pin "6") (pinfunction "6_6") (pintype "passive"))
    )
    (net (code "97") (name "/P27") (class "Default")
      (node (ref "CPU1") (pin "28") (pinfunction "P2.7_28") (pintype "passive"))
      (node (ref "J4") (pin "1") (pinfunction "1_1") (pintype "passive"))
      (node (ref "RN7") (pin "5") (pinfunction "5_5") (pintype "passive"))
    )
    (net (code "98") (name "/P30") (class "Default")
      (node (ref "CPU1") (pin "10") (pinfunction "P3.0/RxD_10") (pintype "passive"))
      (node (ref "J3") (pin "8") (pinfunction "8_8") (pintype "passive"))
      (node (ref "P1") (pin "2") (pinfunction "2_2") (pintype "passive"))
    )
    (net (code "99") (name "/P31") (class "Default")
      (node (ref "CPU1") (pin "11") (pinfunction "P3.1/TxD_11") (pintype "passive"))
      (node (ref "J3") (pin "7") (pinfunction "7_7") (pintype "passive"))
      (node (ref "P1") (pin "4") (pinfunction "4_4") (pintype "passive"))
    )
    (net (code "100") (name "/P32") (class "Default")
      (node (ref "CPU1") (pin "12") (pinfunction "P3.2/INT0_12") (pintype "passive"))
      (node (ref "J3") (pin "6") (pinfunction "6_6") (pintype "passive"))
      (node (ref "RN5") (pin "6") (pinfunction "6_6") (pintype "passive"))
    )
    (net (code "101") (name "/P33") (class "Default")
      (node (ref "CPU1") (pin "13") (pinfunction "P3.3/INT1_13") (pintype "passive"))
      (node (ref "J3") (pin "5") (pinfunction "5_5") (pintype "passive"))
      (node (ref "RN5") (pin "5") (pinfunction "5_5") (pintype "passive"))
    )
    (net (code "102") (name "/P34") (class "Default")
      (node (ref "CPU1") (pin "14") (pinfunction "P3.4/T0_14") (pintype "passive"))
      (node (ref "J3") (pin "4") (pinfunction "4_4") (pintype "passive"))
    )
    (net (code "103") (name "/P35") (class "Default")
      (node (ref "CPU1") (pin "15") (pinfunction "P3.5/T1_15") (pintype "passive"))
      (node (ref "J3") (pin "3") (pinfunction "3_3") (pintype "passive"))
      (node (ref "RN8") (pin "7") (pinfunction "7_7") (pintype "passive"))
    )
    (net (code "104") (name "/P36") (class "Default")
      (node (ref "CPU1") (pin "16") (pinfunction "P3.6/WR_16") (pintype "passive"))
      (node (ref "J3") (pin "2") (pinfunction "2_2") (pintype "passive"))
      (node (ref "RN8") (pin "6") (pinfunction "6_6") (pintype "passive"))
    )
    (net (code "105") (name "/P37") (class "Default")
      (node (ref "CPU1") (pin "17") (pinfunction "P3.7/RD_17") (pintype "passive"))
      (node (ref "J3") (pin "1") (pinfunction "1_1") (pintype "passive"))
      (node (ref "RN8") (pin "5") (pinfunction "5_5") (pintype "passive"))
    )
    (net (code "106") (name "/RST") (class "Default")
      (node (ref "C7") (pin "2") (pinfunction "2_2") (pintype "passive"))
      (node (ref "CPU1") (pin "9") (pinfunction "RST/VPD_9") (pintype "passive"))
      (node (ref "R8") (pin "1") (pinfunction "1_1") (pintype "passive"))
      (node (ref "RSTK1") (pin "2") (pinfunction "2_2") (pintype "passive"))
    )
    (net (code "107") (name "/RXD-U") (class "Default")
      (node (ref "DV1") (pin "1") (pinfunction "1_1") (pintype "passive"))
      (node (ref "P1") (pin "1") (pinfunction "1_1") (pintype "passive"))
    )
    (net (code "108") (name "/TXD-U") (class "Default")
      (node (ref "P1") (pin "3") (pinfunction "3_3") (pintype "passive"))
      (node (ref "U1") (pin "3") (pinfunction "RXD_3") (pintype "passive"))
    )
    (net (code "109") (name "5V") (class "Default")
      (node (ref "C1") (pin "1") (pintype "passive"))
      (node (ref "C10") (pin "2") (pintype "passive"))
      (node (ref "C11") (pin "2") (pintype "passive"))
      (node (ref "C12") (pin "2") (pintype "passive"))
      (node (ref "C13") (pin "2") (pintype "passive"))
      (node (ref "C14") (pin "2") (pintype "passive"))
      (node (ref "C15") (pin "2") (pintype "passive"))
      (node (ref "C16") (pin "2") (pintype "passive"))
      (node (ref "C7") (pin "1") (pinfunction "1_1") (pintype "passive"))
      (node (ref "C9") (pin "2") (pintype "passive"))
      (node (ref "CPU1") (pin "40") (pinfunction "VCC_40") (pintype "passive"))
      (node (ref "P3") (pin "1") (pinfunction "1_1") (pintype "passive"))
      (node (ref "P4") (pin "1") (pinfunction "1_1") (pintype "passive"))
      (node (ref "Q1") (pin "D") (pinfunction "D_D") (pintype "input"))
      (node (ref "R1") (pin "1") (pinfunction "1_1") (pintype "passive"))
      (node (ref "R10") (pin "1") (pinfunction "1_1") (pintype "passive"))
      (node (ref "R11") (pin "1") (pinfunction "1_1") (pintype "passive"))
      (node (ref "R12") (pin "1") (pinfunction "1_1") (pintype "passive"))
      (node (ref "R4") (pin "2") (pinfunction "2_2") (pintype "passive"))
      (node (ref "R9") (pin "1") (pinfunction "1_1") (pintype "passive"))
      (node (ref "RN1") (pin "1") (pinfunction "1_1") (pintype "passive"))
      (node (ref "RN1") (pin "2") (pinfunction "2_2") (pintype "passive"))
      (node (ref "RN1") (pin "3") (pinfunction "3_3") (pintype "passive"))
      (node (ref "RN1") (pin "4") (pinfunction "4_4") (pintype "passive"))
      (node (ref "RN2") (pin "5") (pinfunction "5_5") (pintype "passive"))
      (node (ref "RN2") (pin "6") (pinfunction "6_6") (pintype "passive"))
      (node (ref "RN2") (pin "7") (pinfunction "7_7") (pintype "passive"))
      (node (ref "RN2") (pin "8") (pinfunction "8_8") (pintype "passive"))
      (node (ref "RN3") (pin "5") (pinfunction "5_5") (pintype "passive"))
      (node (ref "RN3") (pin "6") (pinfunction "6_6") (pintype "passive"))
      (node (ref "RN3") (pin "7") (pinfunction "7_7") (pintype "passive"))
      (node (ref "RN3") (pin "8") (pinfunction "8_8") (pintype "passive"))
      (node (ref "RN4") (pin "1") (pinfunction "1_1") (pintype "passive"))
      (node (ref "RN4") (pin "2") (pinfunction "2_2") (pintype "passive"))
      (node (ref "RN4") (pin "3") (pinfunction "3_3") (pintype "passive"))
      (node (ref "RN4") (pin "4") (pinfunction "4_4") (pintype "passive"))
      (node (ref "RN5") (pin "1") (pinfunction "1_1") (pintype "passive"))
      (node (ref "RN5") (pin "2") (pinfunction "2_2") (pintype "passive"))
      (node (ref "RN5") (pin "3") (pinfunction "3_3") (pintype "passive"))
      (node (ref "RN5") (pin "4") (pinfunction "4_4") (pintype "passive"))
      (node (ref "RN6") (pin "1") (pinfunction "1_1") (pintype "passive"))
      (node (ref "RN6") (pin "2") (pinfunction "2_2") (pintype "passive"))
      (node (ref "RN6") (pin "3") (pinfunction "3_3") (pintype "passive"))
      (node (ref "RN6") (pin "4") (pinfunction "4_4") (pintype "passive"))
      (node (ref "RN7") (pin "1") (pinfunction "1_1") (pintype "passive"))
      (node (ref "RN7") (pin "2") (pinfunction "2_2") (pintype "passive"))
      (node (ref "RN7") (pin "3") (pinfunction "3_3") (pintype "passive"))
      (node (ref "RN7") (pin "4") (pinfunction "4_4") (pintype "passive"))
      (node (ref "RN8") (pin "1") (pinfunction "1_1") (pintype "passive"))
      (node (ref "RN8") (pin "2") (pinfunction "2_2") (pintype "passive"))
      (node (ref "RN8") (pin "3") (pinfunction "3_3") (pintype "passive"))
      (node (ref "RN8") (pin "4") (pinfunction "4_4") (pintype "passive"))
      (node (ref "RSTK1") (pin "1") (pinfunction "1_1") (pintype "passive"))
      (node (ref "U4") (pin "19") (pinfunction "V+_19") (pintype "passive"))
      (node (ref "U5") (pin "19") (pinfunction "V+_19") (pintype "passive"))
      (node (ref "U6") (pin "19") (pinfunction "V+_19") (pintype "passive"))
      (node (ref "U7") (pin "19") (pinfunction "V+_19") (pintype "passive"))
    )
    (net (code "110") (name "GND") (class "Default")
      (node (ref "C1") (pin "2") (pintype "passive"))
      (node (ref "C10") (pin "1") (pintype "passive"))
      (node (ref "C11") (pin "1") (pintype "passive"))
      (node (ref "C12") (pin "1") (pintype "passive"))
      (node (ref "C13") (pin "1") (pintype "passive"))
      (node (ref "C14") (pin "1") (pintype "passive"))
      (node (ref "C15") (pin "1") (pintype "passive"))
      (node (ref "C16") (pin "1") (pintype "passive"))
      (node (ref "C2") (pin "1") (pintype "passive"))
      (node (ref "C3") (pin "1") (pintype "passive"))
      (node (ref "C4") (pin "2") (pintype "passive"))
      (node (ref "C5") (pin "1") (pintype "passive"))
      (node (ref "C6") (pin "2") (pintype "passive"))
      (node (ref "C9") (pin "1") (pintype "passive"))
      (node (ref "CP1") (pin "2") (pintype "passive"))
      (node (ref "CPU1") (pin "20") (pinfunction "GND_20") (pintype "passive"))
      (node (ref "LED1") (pin "2") (pinfunction "K_2") (pintype "passive"))
      (node (ref "P2") (pin "2") (pinfunction "2_2") (pintype "passive"))
      (node (ref "P3") (pin "2") (pinfunction "2_2") (pintype "passive"))
      (node (ref "P4") (pin "2") (pinfunction "2_2") (pintype "passive"))
      (node (ref "R2") (pin "2") (pinfunction "2_2") (pintype "passive"))
      (node (ref "R8") (pin "2") (pinfunction "2_2") (pintype "passive"))
      (node (ref "U1") (pin "1") (pinfunction "GND_1") (pintype "passive"))
      (node (ref "U2") (pin "2") (pinfunction "2_2") (pintype "passive"))
      (node (ref "U4") (pin "4") (pinfunction "GND_4") (pintype "passive"))
      (node (ref "U4") (pin "9") (pinfunction "GND_9") (pintype "passive"))
      (node (ref "U5") (pin "4") (pinfunction "GND_4") (pintype "passive"))
      (node (ref "U5") (pin "9") (pinfunction "GND_9") (pintype "passive"))
      (node (ref "U6") (pin "4") (pinfunction "GND_4") (pintype "passive"))
      (node (ref "U6") (pin "9") (pinfunction "GND_9") (pintype "passive"))
      (node (ref "U7") (pin "4") (pinfunction "GND_4") (pintype "passive"))
      (node (ref "U7") (pin "9") (pinfunction "GND_9") (pintype "passive"))
      (node (ref "USB1") (pin "5") (pinfunction "5_5") (pintype "passive"))
    )
    (net (code "111") (name "Net-(CPU1-EA{slash}Vpp)") (class "Default")
      (node (ref "CPU1") (pin "31") (pinfunction "EA/Vpp_31") (pintype "passive"))
      (node (ref "R4") (pin "1") (pinfunction "1_1") (pintype "passive"))
    )
    (net (code "112") (name "Net-(CPU1-XTAL1)") (class "Default")
      (node (ref "C6") (pin "1") (pintype "passive"))
      (node (ref "CPU1") (pin "19") (pinfunction "XTAL1_19") (pintype "passive"))
      (node (ref "Y1") (pin "1") (pinfunction "1_1") (pintype "passive"))
    )
    (net (code "113") (name "Net-(CPU1-XTAL2)") (class "Default")
      (node (ref "C4") (pin "1") (pintype "passive"))
      (node (ref "CPU1") (pin "18") (pinfunction "XTAL2_18") (pintype "passive"))
      (node (ref "Y1") (pin "2") (pinfunction "2_2") (pintype "passive"))
    )
    (net (code "114") (name "Net-(LED1-A)") (class "Default")
      (node (ref "LED1") (pin "1") (pinfunction "A_1") (pintype "passive"))
      (node (ref "R1") (pin "2") (pinfunction "2_2") (pintype "passive"))
    )
    (net (code "115") (name "Net-(Q1-PadG)") (class "Default")
      (node (ref "Q1") (pin "G") (pinfunction "G_G") (pintype "input"))
      (node (ref "R2") (pin "1") (pinfunction "1_1") (pintype "passive"))
      (node (ref "R3") (pin "2") (pinfunction "2_2") (pintype "passive"))
    )
    (net (code "116") (name "Net-(Q2-Padc)") (class "Default")
      (node (ref "Q2") (pin "c") (pinfunction "c_c") (pintype "passive"))
      (node (ref "R3") (pin "1") (pinfunction "1_1") (pintype "passive"))
    )
    (net (code "117") (name "Net-(Q2-b)") (class "Default")
      (node (ref "Q2") (pin "B") (pinfunction "b_B") (pintype "passive"))
      (node (ref "R5") (pin "1") (pinfunction "1_1") (pintype "passive"))
    )
    (net (code "118") (name "Net-(R6-Pad1)") (class "Default")
      (node (ref "R6") (pin "1") (pinfunction "1_1") (pintype "passive"))
      (node (ref "USB1") (pin "2") (pinfunction "2_2") (pintype "passive"))
    )
    (net (code "119") (name "Net-(R7-Pad1)") (class "Default")
      (node (ref "R7") (pin "1") (pinfunction "1_1") (pintype "passive"))
      (node (ref "USB1") (pin "3") (pinfunction "3_3") (pintype "passive"))
    )
    (net (code "120") (name "Net-(U1-DTR#)") (class "Default")
      (node (ref "Q2") (pin "e") (pinfunction "e_e") (pintype "passive"))
      (node (ref "U1") (pin "13") (pinfunction "DTR#_13") (pintype "passive"))
    )
    (net (code "121") (name "Net-(U1-RTS#)") (class "Default")
      (node (ref "R5") (pin "2") (pinfunction "2_2") (pintype "passive"))
      (node (ref "U1") (pin "14") (pinfunction "RTS#_14") (pintype "passive"))
    )
    (net (code "122") (name "Net-(U1-TXD)") (class "Default")
      (node (ref "DV1") (pin "2") (pinfunction "2_2") (pintype "passive"))
      (node (ref "U1") (pin "2") (pinfunction "TXD_2") (pintype "passive"))
    )
    (net (code "123") (name "Net-(U1-V3)") (class "Default")
      (node (ref "C3") (pin "2") (pintype "passive"))
      (node (ref "U1") (pin "4") (pinfunction "V3_4") (pintype "passive"))
    )
    (net (code "124") (name "Net-(U3-G)") (class "Default")
      (node (ref "C8") (pin "1") (pintype "passive"))
      (node (ref "U3") (pin "1") (pinfunction "G_1") (pintype "passive"))
    )
    (net (code "125") (name "Net-(U4-ISET)") (class "Default")
      (node (ref "R11") (pin "2") (pinfunction "2_2") (pintype "passive"))
      (node (ref "U4") (pin "18") (pinfunction "ISET_18") (pintype "passive"))
    )
    (net (code "126") (name "Net-(U5-ISET)") (class "Default")
      (node (ref "R10") (pin "2") (pinfunction "2_2") (pintype "passive"))
      (node (ref "U5") (pin "18") (pinfunction "ISET_18") (pintype "passive"))
    )
    (net (code "127") (name "Net-(U6-ISET)") (class "Default")
      (node (ref "R9") (pin "2") (pinfunction "2_2") (pintype "passive"))
      (node (ref "U6") (pin "18") (pinfunction "ISET_18") (pintype "passive"))
    )
    (net (code "128") (name "Net-(U7-ISET)") (class "Default")
      (node (ref "R12") (pin "2") (pinfunction "2_2") (pintype "passive"))
      (node (ref "U7") (pin "18") (pinfunction "ISET_18") (pintype "passive"))
    )
    (net (code "129") (name "unconnected-(CPU1-ALE{slash}PROG-Pad30)") (class "Default")
      (node (ref "CPU1") (pin "30") (pinfunction "ALE/PROG_30") (pintype "passive+no_connect"))
    )
    (net (code "130") (name "unconnected-(CPU1-PSEN-Pad29)") (class "Default")
      (node (ref "CPU1") (pin "29") (pinfunction "PSEN_29") (pintype "passive+no_connect"))
    )
    (net (code "131") (name "unconnected-(POWER1-NO1-Pad3)") (class "Default")
      (node (ref "POWER1") (pin "3") (pinfunction "NO1_3") (pintype "passive"))
    )
    (net (code "132") (name "unconnected-(POWER1-NO2-Pad4)") (class "Default")
      (node (ref "POWER1") (pin "4") (pinfunction "NO2_4") (pintype "passive"))
    )
    (net (code "133") (name "unconnected-(RN5-Pad7)") (class "Default")
      (node (ref "RN5") (pin "7") (pinfunction "7_7") (pintype "passive+no_connect"))
    )
    (net (code "134") (name "unconnected-(RN5-Pad8)") (class "Default")
      (node (ref "RN5") (pin "8") (pinfunction "8_8") (pintype "passive+no_connect"))
    )
    (net (code "135") (name "unconnected-(RN8-Pad8)") (class "Default")
      (node (ref "RN8") (pin "8") (pinfunction "8_8") (pintype "passive+no_connect"))
    )
    (net (code "136") (name "unconnected-(U1-CTS#-Pad9)") (class "Default")
      (node (ref "U1") (pin "9") (pinfunction "CTS#_9") (pintype "passive"))
    )
    (net (code "137") (name "unconnected-(U1-DCD#-Pad12)") (class "Default")
      (node (ref "U1") (pin "12") (pinfunction "DCD#_12") (pintype "passive"))
    )
    (net (code "138") (name "unconnected-(U1-DSR#-Pad10)") (class "Default")
      (node (ref "U1") (pin "10") (pinfunction "DSR#_10") (pintype "passive"))
    )
    (net (code "139") (name "unconnected-(U1-R232-Pad15)") (class "Default")
      (node (ref "U1") (pin "15") (pinfunction "R232_15") (pintype "passive"))
    )
    (net (code "140") (name "unconnected-(U1-RI#-Pad11)") (class "Default")
      (node (ref "U1") (pin "11") (pinfunction "RI#_11") (pintype "passive"))
    )
    (net (code "141") (name "unconnected-(U1-XI-Pad7)") (class "Default")
      (node (ref "U1") (pin "7") (pinfunction "XI_7") (pintype "passive"))
    )
    (net (code "142") (name "unconnected-(U1-XO-Pad8)") (class "Default")
      (node (ref "U1") (pin "8") (pinfunction "XO_8") (pintype "passive"))
    )
    (net (code "143") (name "unconnected-(USB1-Pad4)") (class "Default")
      (node (ref "USB1") (pin "4") (pinfunction "4_4") (pintype "passive+no_connect"))
    )
  )
)
